# config-serdes.net
KiCad netlist of a schematic drawn in Altium Designer
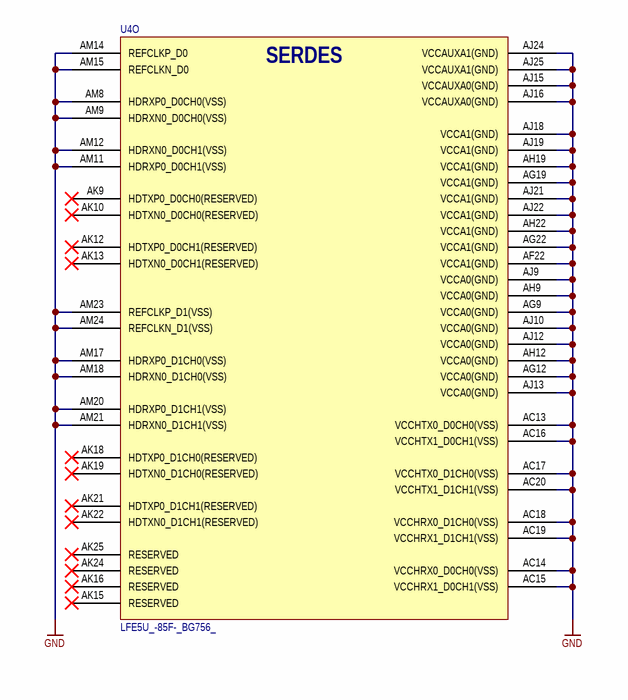
[diagram p0: config-serdes.SchDoc]

(export (version "E")
  (design (tool "Eeschema 10.0.6"))
  (components
    (comp (ref "U4")
      (value "LFE5U_-85F-_BG756_")
      (footprint "lattice:caBGA756")
      (description "ECP5 FPGA, 85k LUT, 756-caBGA")
      (fields (field (name "MANUFACTURER") "Lattice Semiconductor"))
      (libsource (lib "lattice") (part "LFE5U_-85F-_BG756_"))
    )
  )
  (nets
    (net (code "1") (name "GND") (class "Default")
      (node (ref "U4") (pin "AC13") (pinfunction "VCCHTX0_D0CH0(VSS)_AC13") (pintype "power_in"))
      (node (ref "U4") (pin "AC14") (pinfunction "VCCHRX0_D0CH0(VSS)_AC14") (pintype "power_in"))
      (node (ref "U4") (pin "AC15") (pinfunction "VCCHRX1_D0CH1(VSS)_AC15") (pintype "power_in"))
      (node (ref "U4") (pin "AC16") (pinfunction "VCCHTX1_D0CH1(VSS)_AC16") (pintype "power_in"))
      (node (ref "U4") (pin "AC17") (pinfunction "VCCHTX0_D1CH0(VSS)_AC17") (pintype "power_in"))
      (node (ref "U4") (pin "AC18") (pinfunction "VCCHRX0_D1CH0(VSS)_AC18") (pintype "power_in"))
      (node (ref "U4") (pin "AC19") (pinfunction "VCCHRX1_D1CH1(VSS)_AC19") (pintype "power_in"))
      (node (ref "U4") (pin "AC20") (pinfunction "VCCHTX1_D1CH1(VSS)_AC20") (pintype "power_in"))
      (node (ref "U4") (pin "AF22") (pinfunction "VCCA1(GND)_AF22") (pintype "power_in"))
      (node (ref "U4") (pin "AG12") (pinfunction "VCCA0(GND)_AG12") (pintype "power_in"))
      (node (ref "U4") (pin "AG19") (pinfunction "VCCA1(GND)_AG19") (pintype "power_in"))
      (node (ref "U4") (pin "AG22") (pinfunction "VCCA1(GND)_AG22") (pintype "power_in"))
      (node (ref "U4") (pin "AG9") (pinfunction "VCCA0(GND)_AG9") (pintype "power_in"))
      (node (ref "U4") (pin "AH12") (pinfunction "VCCA0(GND)_AH12") (pintype "power_in"))
      (node (ref "U4") (pin "AH19") (pinfunction "VCCA1(GND)_AH19") (pintype "power_in"))
      (node (ref "U4") (pin "AH22") (pinfunction "VCCA1(GND)_AH22") (pintype "power_in"))
      (node (ref "U4") (pin "AH9") (pinfunction "VCCA0(GND)_AH9") (pintype "power_in"))
      (node (ref "U4") (pin "AJ10") (pinfunction "VCCA0(GND)_AJ10") (pintype "power_in"))
      (node (ref "U4") (pin "AJ12") (pinfunction "VCCA0(GND)_AJ12") (pintype "power_in"))
      (node (ref "U4") (pin "AJ13") (pinfunction "VCCA0(GND)_AJ13") (pintype "power_in"))
      (node (ref "U4") (pin "AJ15") (pinfunction "VCCAUXA0(GND)_AJ15") (pintype "power_in"))
      (node (ref "U4") (pin "AJ16") (pinfunction "VCCAUXA0(GND)_AJ16") (pintype "power_in"))
      (node (ref "U4") (pin "AJ18") (pinfunction "VCCA1(GND)_AJ18") (pintype "power_in"))
      (node (ref "U4") (pin "AJ19") (pinfunction "VCCA1(GND)_AJ19") (pintype "power_in"))
      (node (ref "U4") (pin "AJ21") (pinfunction "VCCA1(GND)_AJ21") (pintype "power_in"))
      (node (ref "U4") (pin "AJ22") (pinfunction "VCCA1(GND)_AJ22") (pintype "power_in"))
      (node (ref "U4") (pin "AJ24") (pinfunction "VCCAUXA1(GND)_AJ24") (pintype "power_in"))
      (node (ref "U4") (pin "AJ25") (pinfunction "VCCAUXA1(GND)_AJ25") (pintype "power_in"))
      (node (ref "U4") (pin "AJ9") (pinfunction "VCCA0(GND)_AJ9") (pintype "power_in"))
      (node (ref "U4") (pin "AM11") (pinfunction "HDRXP0_D0CH1(VSS)_AM11") (pintype "passive"))
      (node (ref "U4") (pin "AM12") (pinfunction "HDRXN0_D0CH1(VSS)_AM12") (pintype "passive"))
      (node (ref "U4") (pin "AM14") (pinfunction "REFCLKP_D0_AM14") (pintype "passive"))
      (node (ref "U4") (pin "AM15") (pinfunction "REFCLKN_D0_AM15") (pintype "passive"))
      (node (ref "U4") (pin "AM17") (pinfunction "HDRXP0_D1CH0(VSS)_AM17") (pintype "passive"))
      (node (ref "U4") (pin "AM18") (pinfunction "HDRXN0_D1CH0(VSS)_AM18") (pintype "passive"))
      (node (ref "U4") (pin "AM20") (pinfunction "HDRXP0_D1CH1(VSS)_AM20") (pintype "passive"))
      (node (ref "U4") (pin "AM21") (pinfunction "HDRXN0_D1CH1(VSS)_AM21") (pintype "passive"))
      (node (ref "U4") (pin "AM23") (pinfunction "REFCLKP_D1(VSS)_AM23") (pintype "passive"))
      (node (ref "U4") (pin "AM24") (pinfunction "REFCLKN_D1(VSS)_AM24") (pintype "passive"))
      (node (ref "U4") (pin "AM8") (pinfunction "HDRXP0_D0CH0(VSS)_AM8") (pintype "passive"))
      (node (ref "U4") (pin "AM9") (pinfunction "HDRXN0_D0CH0(VSS)_AM9") (pintype "passive"))
    )
    (net (code "2") (name "unconnected-(U4O-HDTXN0_D0CH0(RESERVED)-PadAK10)") (class "Default")
      (node (ref "U4") (pin "AK10") (pinfunction "HDTXN0_D0CH0(RESERVED)_AK10") (pintype "passive+no_connect"))
    )
    (net (code "3") (name "unconnected-(U4O-HDTXN0_D0CH1(RESERVED)-PadAK13)") (class "Default")
      (node (ref "U4") (pin "AK13") (pinfunction "HDTXN0_D0CH1(RESERVED)_AK13") (pintype "passive+no_connect"))
    )
    (net (code "4") (name "unconnected-(U4O-HDTXN0_D1CH0(RESERVED)-PadAK19)") (class "Default")
      (node (ref "U4") (pin "AK19") (pinfunction "HDTXN0_D1CH0(RESERVED)_AK19") (pintype "passive+no_connect"))
    )
    (net (code "5") (name "unconnected-(U4O-HDTXN0_D1CH1(RESERVED)-PadAK22)") (class "Default")
      (node (ref "U4") (pin "AK22") (pinfunction "HDTXN0_D1CH1(RESERVED)_AK22") (pintype "passive+no_connect"))
    )
    (net (code "6") (name "unconnected-(U4O-HDTXP0_D0CH0(RESERVED)-PadAK9)") (class "Default")
      (node (ref "U4") (pin "AK9") (pinfunction "HDTXP0_D0CH0(RESERVED)_AK9") (pintype "passive+no_connect"))
    )
    (net (code "7") (name "unconnected-(U4O-HDTXP0_D0CH1(RESERVED)-PadAK12)") (class "Default")
      (node (ref "U4") (pin "AK12") (pinfunction "HDTXP0_D0CH1(RESERVED)_AK12") (pintype "passive+no_connect"))
    )
    (net (code "8") (name "unconnected-(U4O-HDTXP0_D1CH0(RESERVED)-PadAK18)") (class "Default")
      (node (ref "U4") (pin "AK18") (pinfunction "HDTXP0_D1CH0(RESERVED)_AK18") (pintype "passive+no_connect"))
    )
    (net (code "9") (name "unconnected-(U4O-HDTXP0_D1CH1(RESERVED)-PadAK21)") (class "Default")
      (node (ref "U4") (pin "AK21") (pinfunction "HDTXP0_D1CH1(RESERVED)_AK21") (pintype "passive+no_connect"))
    )
    (net (code "10") (name "unconnected-(U4O-RESERVED-PadAK15)") (class "Default")
      (node (ref "U4") (pin "AK15") (pinfunction "RESERVED_AK15") (pintype "passive+no_connect"))
    )
    (net (code "11") (name "unconnected-(U4O-RESERVED-PadAK16)") (class "Default")
      (node (ref "U4") (pin "AK16") (pinfunction "RESERVED_AK16") (pintype "passive+no_connect"))
    )
    (net (code "12") (name "unconnected-(U4O-RESERVED-PadAK24)") (class "Default")
      (node (ref "U4") (pin "AK24") (pinfunction "RESERVED_AK24") (pintype "passive+no_connect"))
    )
    (net (code "13") (name "unconnected-(U4O-RESERVED-PadAK25)") (class "Default")
      (node (ref "U4") (pin "AK25") (pinfunction "RESERVED_AK25") (pintype "passive+no_connect"))
    )
  )
)
